# POWER.net
KiCad netlist of a schematic drawn in Altium Designer
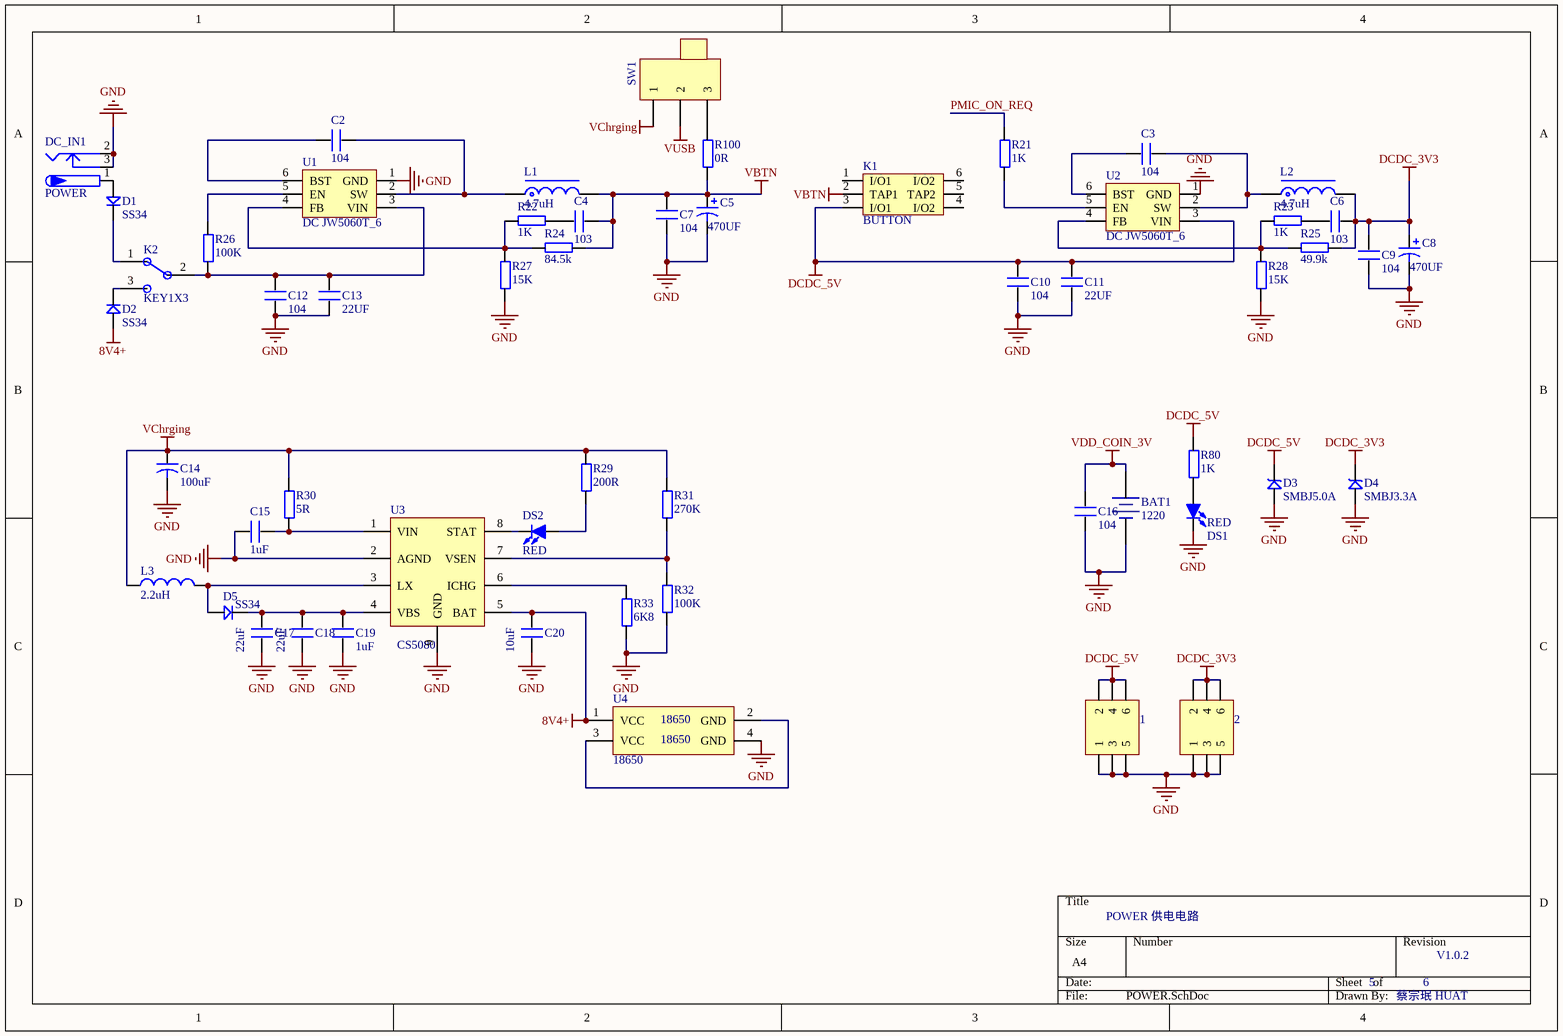
[diagram p0: POWER.SchDoc]

(export (version "E")
  (design (tool "Eeschema 10.0.6"))
  (components
    (comp (ref "1")
      (value "RS232/RS485")
      (footprint "HDR-3X2")
      (description "3*2P接插件")
      (fields (field (name "版权归属") "源创客"))
      (libsource (lib "IMX6UL_ALPHA(底板)_V2.0") (part "Header 3X2"))
    )
    (comp (ref "2")
      (value "RS232/RS485")
      (footprint "HDR-3X2")
      (description "3*2P接插件")
      (fields (field (name "版权归属") "源创客"))
      (libsource (lib "IMX6UL_ALPHA(底板)_V2.0") (part "Header 3X2"))
    )
    (comp (ref "BAT1")
      (value "1220")
      (footprint "CR1220_B")
      (description "微型电池")
      (fields (field (name "版权归属") "源创客"))
      (libsource (lib "IMX6UL_ALPHA(底板)_V2.0") (part "CR-3V"))
    )
    (comp (ref "C2") (value "104") (footprint "C_0603P") (libsource (lib "ZZW封装汇总") (part "C")))
    (comp (ref "C3") (value "104") (footprint "C_0603P") (libsource (lib "ZZW封装汇总") (part "C")))
    (comp (ref "C4") (value "103") (footprint "C_0603P") (libsource (lib "ZZW封装汇总") (part "C")))
    (comp (ref "C5")
      (value "470UF")
      (footprint "CAP2.54M")
      (description "Polarized Capacitor (Radial)")
      (fields (field (name "Comment") "Cap Pol1") (field (name "PUBLISHER") "Altium Limited"))
      (libsource (lib "Miscellaneous Devices") (part "Cap Pol1"))
    )
    (comp (ref "C6") (value "103") (footprint "C_0603P") (libsource (lib "ZZW封装汇总") (part "C")))
    (comp (ref "C7") (value "104") (footprint "C_0603P") (libsource (lib "ZZW封装汇总") (part "C")))
    (comp (ref "C8")
      (value "470UF")
      (footprint "CAP2.54M")
      (description "Polarized Capacitor (Radial)")
      (fields (field (name "Comment") "Cap Pol1") (field (name "PUBLISHER") "Altium Limited"))
      (libsource (lib "Miscellaneous Devices") (part "Cap Pol1"))
    )
    (comp (ref "C9") (value "104") (footprint "C_0603P") (libsource (lib "ZZW封装汇总") (part "C")))
    (comp (ref "C10") (value "104") (footprint "C_0603P") (libsource (lib "ZZW封装汇总") (part "C")))
    (comp (ref "C11") (value "22UF") (footprint "C_0603P") (libsource (lib "ZZW封装汇总") (part "C")))
    (comp (ref "C12") (value "104") (footprint "C_0603P") (libsource (lib "ZZW封装汇总") (part "C")))
    (comp (ref "C13") (value "22UF") (footprint "C_0603P") (libsource (lib "ZZW封装汇总") (part "C")))
    (comp (ref "C14")
      (value "100uF")
      (footprint "CAP2.54M")
      (description "Capacitor")
      (fields (field (name "Comment") "Cap2") (field (name "PUBLISHER") "Altium Limited"))
      (libsource (lib "Miscellaneous Devices") (part "Cap2"))
    )
    (comp (ref "C15") (value "1uF") (footprint "C_0603P") (libsource (lib "ZZW封装汇总") (part "C")))
    (comp (ref "C16") (value "104") (footprint "C_0603P") (libsource (lib "ZZW封装汇总") (part "C")))
    (comp (ref "C17") (value "22uF") (footprint "C_0603P") (libsource (lib "ZZW封装汇总") (part "C")))
    (comp (ref "C18") (value "22uF") (footprint "C_0603P") (libsource (lib "ZZW封装汇总") (part "C")))
    (comp (ref "C19") (value "1uF") (footprint "C_0603P") (libsource (lib "ZZW封装汇总") (part "C")))
    (comp (ref "C20") (value "10uF") (footprint "C_0805") (libsource (lib "ZZW封装汇总") (part "C")))
    (comp (ref "D1")
      (value "SS34")
      (footprint "DIODE 3*5.3")
      (description "1N4148")
      (libsource (lib "ZZW封装汇总") (part "D"))
    )
    (comp (ref "D2")
      (value "SS34")
      (footprint "DIODE 3*5.3")
      (description "1N4148")
      (libsource (lib "ZZW封装汇总") (part "D"))
    )
    (comp (ref "D3")
      (value "SMBJ5.0A")
      (footprint "SMBJ")
      (description "TVS")
      (libsource (lib "IMX6UL_ALPHA(底板)_V2.0") (part "SMBJ"))
    )
    (comp (ref "D4")
      (value "SMBJ3.3A")
      (footprint "SMBJ")
      (description "TVS")
      (libsource (lib "IMX6UL_ALPHA(底板)_V2.0") (part "SMBJ"))
    )
    (comp (ref "D5")
      (value "SS34")
      (footprint "DIODE 3*5.3")
      (description "1N4148")
      (libsource (lib "ZZW封装汇总") (part "D"))
    )
    (comp (ref "DC_IN1")
      (value "POWER")
      (footprint "DC10B")
      (description "低压电源接口")
      (fields (field (name "版权归属") "源创客"))
      (libsource (lib "IMX6UL_ALPHA(底板)_V2.0") (part "P-DC"))
    )
    (comp (ref "DS1")
      (value "RED")
      (footprint "LED 0805R")
      (description "贴片LED")
      (fields (field (name "版权归属") "源创客"))
      (libsource (lib "IMX6UL_ALPHA(底板)_V2.0") (part "LED-SMD"))
    )
    (comp (ref "DS2")
      (value "RED")
      (footprint "LED 0805R")
      (description "贴片LED")
      (fields (field (name "版权归属") "源创客"))
      (libsource (lib "IMX6UL_ALPHA(底板)_V2.0") (part "LED-SMD"))
    )
    (comp (ref "K1") (value "BUTTON") (footprint "BTN8.5*8.5") (libsource (lib "ZZW封装汇总") (part "BUTTON")))
    (comp (ref "K2")
      (value "KEY1X3")
      (footprint "PKEY")
      (libsource (lib "IMX6UL_ALPHA(底板)_V2.0") (part "PKEY"))
    )
    (comp (ref "L1")
      (value "4.7uH")
      (footprint "L-SMD-0420")
      (description "功率屏蔽电感")
      (fields (field (name "版权归属") "源创客"))
      (libsource (lib "IMX6UL_ALPHA(底板)_V2.0") (part "L-CDRH"))
    )
    (comp (ref "L2")
      (value "4.7uH")
      (footprint "L-SMD-0420")
      (description "功率屏蔽电感")
      (fields (field (name "版权归属") "源创客"))
      (libsource (lib "IMX6UL_ALPHA(底板)_V2.0") (part "L-CDRH"))
    )
    (comp (ref "L3")
      (value "2.2uH")
      (footprint "CD74 电感   7*7*4mm贴片")
      (description "Inductor")
      (fields (field (name "PUBLISHER") "Altium Limited"))
      (libsource (lib "ZZW封装汇总") (part "Inductor"))
    )
    (comp (ref "R21") (value "1K") (footprint "R_0603P") (libsource (lib "ZZW封装汇总") (part "R")))
    (comp (ref "R22") (value "1K") (footprint "R_0603P") (libsource (lib "ZZW封装汇总") (part "R")))
    (comp (ref "R23") (value "1K") (footprint "R_0603P") (libsource (lib "ZZW封装汇总") (part "R")))
    (comp (ref "R24") (value "84.5k") (footprint "R_0603P") (libsource (lib "ZZW封装汇总") (part "R")))
    (comp (ref "R25") (value "49.9k") (footprint "R_0603P") (libsource (lib "ZZW封装汇总") (part "R")))
    (comp (ref "R26") (value "100K") (footprint "R_0603P") (libsource (lib "ZZW封装汇总") (part "R")))
    (comp (ref "R27") (value "15K") (footprint "R_0603P") (libsource (lib "ZZW封装汇总") (part "R")))
    (comp (ref "R28") (value "15K") (footprint "R_0603P") (libsource (lib "ZZW封装汇总") (part "R")))
    (comp (ref "R29") (value "200R") (footprint "R_0603P") (libsource (lib "ZZW封装汇总") (part "R")))
    (comp (ref "R30") (value "5R") (footprint "R_0805") (libsource (lib "ZZW封装汇总") (part "R")))
    (comp (ref "R31") (value "270K") (footprint "R_0603P") (libsource (lib "ZZW封装汇总") (part "R")))
    (comp (ref "R32") (value "100K") (footprint "R_0603P") (libsource (lib "ZZW封装汇总") (part "R")))
    (comp (ref "R33") (value "6K8") (footprint "R_0603P") (libsource (lib "ZZW封装汇总") (part "R")))
    (comp (ref "R80") (value "1K") (footprint "R_0603P") (libsource (lib "ZZW封装汇总") (part "R")))
    (comp (ref "R100") (value "0R") (footprint "R_0805") (libsource (lib "ZZW封装汇总") (part "R")))
    (comp (ref "SW1")
      (value "switch")
      (footprint "三脚拨动开关SS12D00G4")
      (libsource (lib "ZZW封装汇总") (part "3脚拔动开关"))
    )
    (comp (ref "U1")
      (value "DC JW5060T_6")
      (footprint "SOT23-6N")
      (description "DC降压芯片")
      (libsource (lib "IMX6UL_ALPHA(底板)_V2.0") (part "DC JW5060T_6"))
    )
    (comp (ref "U2")
      (value "DC JW5060T_6")
      (footprint "SOT23-6N")
      (description "DC降压芯片")
      (libsource (lib "IMX6UL_ALPHA(底板)_V2.0") (part "DC JW5060T_6"))
    )
    (comp (ref "U3")
      (value "CS5080")
      (footprint "ESOP8   IP5306")
      (description "5V输入8V4输出充电器IC")
      (libsource (lib "ZZW封装汇总") (part "CS5080 5V输入8V4输出充电器IC"))
    )
    (comp (ref "U4")
      (value "18650")
      (footprint "18650 2节电池座 PCB插脚")
      (libsource (lib "ZZW封装汇总") (part "18650 2节电池座 PCB插脚"))
    )
  )
  (nets
    (net (code "1") (name "/PMIC_ON_REQ") (class "Default") (node (ref "R21") (pin "2") (pintype "passive")))
    (net (code "2") (name "8V4+") (class "Default")
      (node (ref "C20") (pin "2") (pintype "passive"))
      (node (ref "D2") (pin "1") (pintype "passive"))
      (node (ref "U3") (pin "5") (pinfunction "BAT_5") (pintype "passive"))
      (node (ref "U4") (pin "1") (pinfunction "VCC_1") (pintype "passive"))
    )
    (net (code "3") (name "DCDC_3V3") (class "Default")
      (node (ref "2") (pin "2") (pinfunction "2_2") (pintype "passive"))
      (node (ref "2") (pin "4") (pinfunction "4_4") (pintype "passive"))
      (node (ref "2") (pin "6") (pinfunction "6_6") (pintype "passive"))
      (node (ref "C6") (pin "1") (pintype "passive"))
      (node (ref "C8") (pin "1") (pinfunction "1_1") (pintype "passive"))
      (node (ref "C9") (pin "2") (pintype "passive"))
      (node (ref "D4") (pin "2") (pintype "passive"))
      (node (ref "L2") (pin "2") (pinfunction "2_2") (pintype "passive"))
      (node (ref "R25") (pin "1") (pintype "passive"))
    )
    (net (code "4") (name "DCDC_5V") (class "Default")
      (node (ref "1") (pin "2") (pinfunction "2_2") (pintype "passive"))
      (node (ref "1") (pin "4") (pinfunction "4_4") (pintype "passive"))
      (node (ref "1") (pin "6") (pinfunction "6_6") (pintype "passive"))
      (node (ref "C10") (pin "2") (pintype "passive"))
      (node (ref "C11") (pin "2") (pintype "passive"))
      (node (ref "D3") (pin "2") (pintype "passive"))
      (node (ref "K1") (pin "3") (pinfunction "I/O1_3") (pintype "passive"))
      (node (ref "R80") (pin "2") (pintype "passive"))
      (node (ref "U2") (pin "3") (pinfunction "VIN_3") (pintype "passive"))
    )
    (net (code "5") (name "GND") (class "Default")
      (node (ref "1") (pin "1") (pinfunction "1_1") (pintype "passive"))
      (node (ref "1") (pin "3") (pinfunction "3_3") (pintype "passive"))
      (node (ref "1") (pin "5") (pinfunction "5_5") (pintype "passive"))
      (node (ref "2") (pin "1") (pinfunction "1_1") (pintype "passive"))
      (node (ref "2") (pin "3") (pinfunction "3_3") (pintype "passive"))
      (node (ref "2") (pin "5") (pinfunction "5_5") (pintype "passive"))
      (node (ref "BAT1") (pin "2") (pinfunction "DC-_2") (pintype "passive"))
      (node (ref "C10") (pin "1") (pintype "passive"))
      (node (ref "C11") (pin "1") (pintype "passive"))
      (node (ref "C12") (pin "1") (pintype "passive"))
      (node (ref "C13") (pin "1") (pintype "passive"))
      (node (ref "C14") (pin "2") (pinfunction "2_2") (pintype "passive"))
      (node (ref "C15") (pin "1") (pintype "passive"))
      (node (ref "C16") (pin "1") (pintype "passive"))
      (node (ref "C17") (pin "1") (pintype "passive"))
      (node (ref "C18") (pin "1") (pintype "passive"))
      (node (ref "C19") (pin "1") (pintype "passive"))
      (node (ref "C20") (pin "1") (pintype "passive"))
      (node (ref "C5") (pin "2") (pinfunction "2_2") (pintype "passive"))
      (node (ref "C7") (pin "1") (pintype "passive"))
      (node (ref "C8") (pin "2") (pinfunction "2_2") (pintype "passive"))
      (node (ref "C9") (pin "1") (pintype "passive"))
      (node (ref "D3") (pin "1") (pintype "passive"))
      (node (ref "D4") (pin "1") (pintype "passive"))
      (node (ref "DC_IN1") (pin "2") (pintype "power_in"))
      (node (ref "DC_IN1") (pin "3") (pintype "power_in"))
      (node (ref "DS1") (pin "2") (pinfunction "K_2") (pintype "passive"))
      (node (ref "R27") (pin "1") (pintype "passive"))
      (node (ref "R28") (pin "1") (pintype "passive"))
      (node (ref "R32") (pin "1") (pintype "passive"))
      (node (ref "R33") (pin "1") (pintype "passive"))
      (node (ref "U1") (pin "1") (pinfunction "GND_1") (pintype "passive"))
      (node (ref "U2") (pin "1") (pinfunction "GND_1") (pintype "passive"))
      (node (ref "U3") (pin "2") (pinfunction "AGND_2") (pintype "passive"))
      (node (ref "U3") (pin "9") (pinfunction "GND_9") (pintype "passive"))
      (node (ref "U4") (pin "4") (pinfunction "GND_4") (pintype "passive"))
    )
    (net (code "6") (name "Net-(C4-Pad2)") (class "Default")
      (node (ref "C4") (pin "2") (pintype "passive"))
      (node (ref "R22") (pin "1") (pintype "passive"))
    )
    (net (code "7") (name "Net-(C6-Pad2)") (class "Default")
      (node (ref "C6") (pin "2") (pintype "passive"))
      (node (ref "R23") (pin "1") (pintype "passive"))
    )
    (net (code "8") (name "Net-(D1-Pad1)") (class "Default")
      (node (ref "D1") (pin "1") (pintype "passive"))
      (node (ref "DC_IN1") (pin "1") (pintype "power_in"))
    )
    (net (code "9") (name "Net-(D1-Pad2)") (class "Default")
      (node (ref "D1") (pin "2") (pintype "passive"))
      (node (ref "K2") (pin "1") (pintype "passive"))
    )
    (net (code "10") (name "Net-(D2-Pad2)") (class "Default")
      (node (ref "D2") (pin "2") (pintype "passive"))
      (node (ref "K2") (pin "3") (pintype "passive"))
    )
    (net (code "11") (name "Net-(DS1-A)") (class "Default")
      (node (ref "DS1") (pin "1") (pinfunction "A_1") (pintype "passive"))
      (node (ref "R80") (pin "1") (pintype "passive"))
    )
    (net (code "12") (name "Net-(DS2-A)") (class "Default")
      (node (ref "DS2") (pin "1") (pinfunction "A_1") (pintype "passive"))
      (node (ref "R29") (pin "1") (pintype "passive"))
    )
    (net (code "13") (name "Net-(DS2-K)") (class "Default")
      (node (ref "DS2") (pin "2") (pinfunction "K_2") (pintype "passive"))
      (node (ref "U3") (pin "8") (pinfunction "STAT_8") (pintype "passive"))
    )
    (net (code "14") (name "Net-(R100-Pad2)") (class "Default")
      (node (ref "R100") (pin "2") (pintype "passive"))
      (node (ref "SW1") (pin "3") (pinfunction "3_3") (pintype "passive"))
    )
    (net (code "15") (name "Net-(U1-BST)") (class "Default")
      (node (ref "C2") (pin "1") (pintype "passive"))
      (node (ref "U1") (pin "6") (pinfunction "BST_6") (pintype "passive"))
    )
    (net (code "16") (name "Net-(U1-EN)") (class "Default")
      (node (ref "R26") (pin "2") (pintype "passive"))
      (node (ref "U1") (pin "5") (pinfunction "EN_5") (pintype "passive"))
    )
    (net (code "17") (name "Net-(U1-FB)") (class "Default")
      (node (ref "R22") (pin "2") (pintype "passive"))
      (node (ref "R24") (pin "2") (pintype "passive"))
      (node (ref "R27") (pin "2") (pintype "passive"))
      (node (ref "U1") (pin "4") (pinfunction "FB_4") (pintype "passive"))
    )
    (net (code "18") (name "Net-(U1-SW)") (class "Default")
      (node (ref "C2") (pin "2") (pintype "passive"))
      (node (ref "L1") (pin "1") (pinfunction "1_1") (pintype "passive"))
      (node (ref "U1") (pin "2") (pinfunction "SW_2") (pintype "passive"))
    )
    (net (code "19") (name "Net-(U1-VIN)") (class "Default")
      (node (ref "C12") (pin "2") (pintype "passive"))
      (node (ref "C13") (pin "2") (pintype "passive"))
      (node (ref "K2") (pin "2") (pintype "passive"))
      (node (ref "R26") (pin "1") (pintype "passive"))
      (node (ref "U1") (pin "3") (pinfunction "VIN_3") (pintype "passive"))
    )
    (net (code "20") (name "Net-(U2-BST)") (class "Default")
      (node (ref "C3") (pin "1") (pintype "passive"))
      (node (ref "U2") (pin "6") (pinfunction "BST_6") (pintype "passive"))
    )
    (net (code "21") (name "Net-(U2-EN)") (class "Default")
      (node (ref "R21") (pin "1") (pintype "passive"))
      (node (ref "U2") (pin "5") (pinfunction "EN_5") (pintype "passive"))
    )
    (net (code "22") (name "Net-(U2-FB)") (class "Default")
      (node (ref "R23") (pin "2") (pintype "passive"))
      (node (ref "R25") (pin "2") (pintype "passive"))
      (node (ref "R28") (pin "2") (pintype "passive"))
      (node (ref "U2") (pin "4") (pinfunction "FB_4") (pintype "passive"))
    )
    (net (code "23") (name "Net-(U2-SW)") (class "Default")
      (node (ref "C3") (pin "2") (pintype "passive"))
      (node (ref "L2") (pin "1") (pinfunction "1_1") (pintype "passive"))
      (node (ref "U2") (pin "2") (pinfunction "SW_2") (pintype "passive"))
    )
    (net (code "24") (name "Net-(U3-ICHG)") (class "Default")
      (node (ref "R33") (pin "2") (pintype "passive"))
      (node (ref "U3") (pin "6") (pinfunction "ICHG_6") (pintype "passive"))
    )
    (net (code "25") (name "Net-(U3-LX)") (class "Default")
      (node (ref "D5") (pin "1") (pintype "passive"))
      (node (ref "L3") (pin "2") (pinfunction "2_2") (pintype "passive"))
      (node (ref "U3") (pin "3") (pinfunction "LX_3") (pintype "passive"))
    )
    (net (code "26") (name "Net-(U3-VBS)") (class "Default")
      (node (ref "C17") (pin "2") (pintype "passive"))
      (node (ref "C18") (pin "2") (pintype "passive"))
      (node (ref "C19") (pin "2") (pintype "passive"))
      (node (ref "D5") (pin "2") (pintype "passive"))
      (node (ref "U3") (pin "4") (pinfunction "VBS_4") (pintype "passive"))
    )
    (net (code "27") (name "Net-(U3-VIN)") (class "Default")
      (node (ref "C15") (pin "2") (pintype "passive"))
      (node (ref "R30") (pin "1") (pintype "passive"))
      (node (ref "U3") (pin "1") (pinfunction "VIN_1") (pintype "passive"))
    )
    (net (code "28") (name "Net-(U3-VSEN)") (class "Default")
      (node (ref "R31") (pin "1") (pintype "passive"))
      (node (ref "R32") (pin "2") (pintype "passive"))
      (node (ref "U3") (pin "7") (pinfunction "VSEN_7") (pintype "passive"))
    )
    (net (code "29") (name "Net-(U4-GND-Pad2)") (class "Default")
      (node (ref "U4") (pin "2") (pinfunction "GND_2") (pintype "passive"))
      (node (ref "U4") (pin "3") (pinfunction "VCC_3") (pintype "passive"))
    )
    (net (code "30") (name "VBTN") (class "Default")
      (node (ref "C4") (pin "1") (pintype "passive"))
      (node (ref "C5") (pin "1") (pinfunction "1_1") (pintype "passive"))
      (node (ref "C7") (pin "2") (pintype "passive"))
      (node (ref "K1") (pin "2") (pinfunction "TAP1_2") (pintype "passive"))
      (node (ref "L1") (pin "2") (pinfunction "2_2") (pintype "passive"))
      (node (ref "R100") (pin "1") (pintype "passive"))
      (node (ref "R24") (pin "1") (pintype "passive"))
    )
    (net (code "31") (name "VChrging") (class "Default")
      (node (ref "C14") (pin "1") (pinfunction "1_1") (pintype "passive"))
      (node (ref "L3") (pin "1") (pinfunction "1_1") (pintype "passive"))
      (node (ref "R29") (pin "2") (pintype "passive"))
      (node (ref "R30") (pin "2") (pintype "passive"))
      (node (ref "R31") (pin "2") (pintype "passive"))
      (node (ref "SW1") (pin "1") (pinfunction "1_1") (pintype "passive"))
    )
    (net (code "32") (name "VDD_COIN_3V") (class "Default")
      (node (ref "BAT1") (pin "1") (pinfunction "DC+_1") (pintype "passive"))
      (node (ref "C16") (pin "2") (pintype "passive"))
    )
    (net (code "33") (name "VUSB") (class "Default")
      (node (ref "SW1") (pin "2") (pinfunction "2_2") (pintype "passive"))
    )
    (net (code "34") (name "unconnected-(K1-I{slash}O1-Pad1)") (class "Default")
      (node (ref "K1") (pin "1") (pinfunction "I/O1_1") (pintype "passive"))
    )
    (net (code "35") (name "unconnected-(K1-I{slash}O2-Pad4)") (class "Default")
      (node (ref "K1") (pin "4") (pinfunction "I/O2_4") (pintype "passive"))
    )
    (net (code "36") (name "unconnected-(K1-I{slash}O2-Pad6)") (class "Default")
      (node (ref "K1") (pin "6") (pinfunction "I/O2_6") (pintype "passive"))
    )
    (net (code "37") (name "unconnected-(K1-TAP2-Pad5)") (class "Default")
      (node (ref "K1") (pin "5") (pinfunction "TAP2_5") (pintype "passive"))
    )
  )
)
